# appleii_blanking_plate.net
KiCad netlist of a schematic drawn in EAGLE
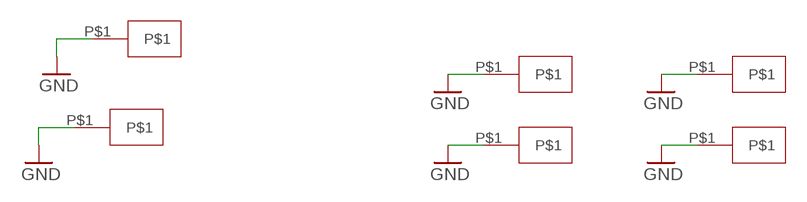
[diagram p0: schematic, sheet 1]

(export (version "E")
  (design (tool "Eeschema 10.0.6"))
  (components
    (comp (ref "U$1")
      (value "EDGEPADEDGEPAD_20MM")
      (footprint "eagle-import:EDGEPAD_20MM")
      (libsource (lib "eagle-import") (part "EDGEPADEDGEPAD_20MM"))
    )
    (comp (ref "U$2")
      (value "EDGEPAD")
      (footprint "eagle-import:EDGEPAD")
      (libsource (lib "eagle-import") (part "EDGEPAD"))
    )
    (comp (ref "U$3")
      (value "EDGEPAD")
      (footprint "eagle-import:EDGEPAD")
      (libsource (lib "eagle-import") (part "EDGEPAD"))
    )
    (comp (ref "U$4")
      (value "EDGEPAD")
      (footprint "eagle-import:EDGEPAD")
      (libsource (lib "eagle-import") (part "EDGEPAD"))
    )
    (comp (ref "U$5")
      (value "EDGEPADEDGEPAD_20MM")
      (footprint "eagle-import:EDGEPAD_20MM")
      (libsource (lib "eagle-import") (part "EDGEPADEDGEPAD_20MM"))
    )
    (comp (ref "U$13")
      (value "EDGEPAD")
      (footprint "eagle-import:EDGEPAD")
      (libsource (lib "eagle-import") (part "EDGEPAD"))
    )
  )
  (nets
    (net (code "1") (name "GND") (class "Default")
      (node (ref "U$1") (pin "P$1") (pinfunction "P$1_P$1") (pintype "bidirectional"))
      (node (ref "U$13") (pin "P$1") (pinfunction "P$1_P$1") (pintype "bidirectional"))
      (node (ref "U$2") (pin "P$1") (pinfunction "P$1_P$1") (pintype "bidirectional"))
      (node (ref "U$3") (pin "P$1") (pinfunction "P$1_P$1") (pintype "bidirectional"))
      (node (ref "U$4") (pin "P$1") (pinfunction "P$1_P$1") (pintype "bidirectional"))
      (node (ref "U$5") (pin "P$1") (pinfunction "P$1_P$1") (pintype "bidirectional"))
    )
  )
)
